# ANTBRAIN.net
KiCad netlist of a schematic drawn in EAGLE
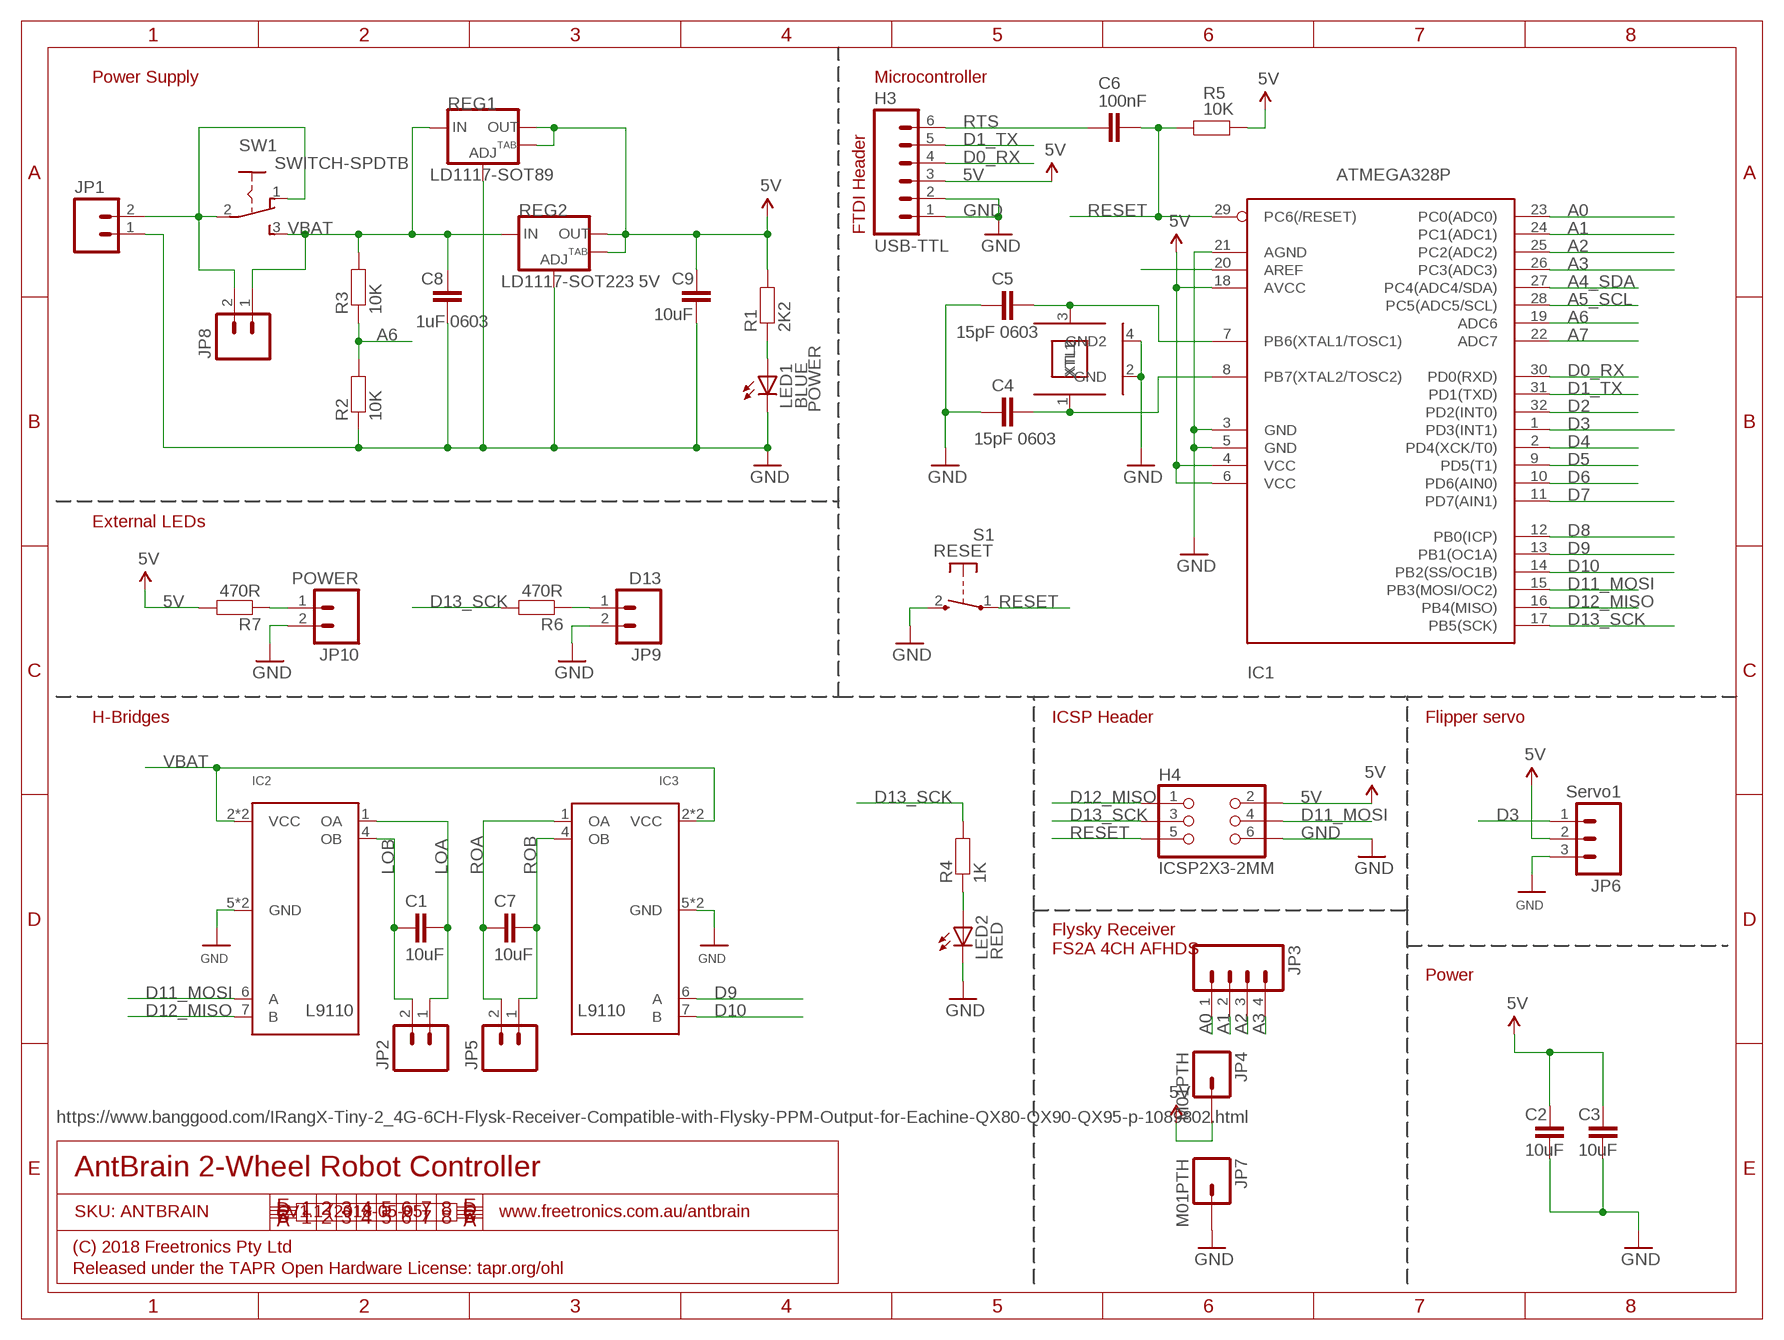
[diagram p0: schematic, sheet 1]

(export (version "E")
  (design (tool "Eeschema 10.0.6"))
  (components
    (comp (ref "C1")
      (value "10uF")
      (footprint "eagle-import:0805")
      (libsource (lib "eagle-import") (part "freetronics-jon_CAP0805"))
    )
    (comp (ref "C2")
      (value "10uF")
      (footprint "eagle-import:0805")
      (libsource (lib "eagle-import") (part "freetronics-jon_CAP0805"))
    )
    (comp (ref "C3")
      (value "10uF")
      (footprint "eagle-import:0805")
      (libsource (lib "eagle-import") (part "freetronics-jon_CAP0805"))
    )
    (comp (ref "C4")
      (value "15pF 0603")
      (footprint "eagle-import:0603")
      (libsource (lib "eagle-import") (part "freetronics-master-v1.1_CAP0603"))
    )
    (comp (ref "C5")
      (value "15pF 0603")
      (footprint "eagle-import:0603")
      (libsource (lib "eagle-import") (part "freetronics-master-v1.1_CAP0603"))
    )
    (comp (ref "C6")
      (value "100nF")
      (footprint "eagle-import:0603")
      (libsource (lib "eagle-import") (part "freetronics-master-v1.1_CAP0603"))
    )
    (comp (ref "C7")
      (value "10uF")
      (footprint "eagle-import:0805")
      (libsource (lib "eagle-import") (part "freetronics-jon_CAP0805"))
    )
    (comp (ref "C8")
      (value "1uF 0603")
      (footprint "eagle-import:0603")
      (libsource (lib "eagle-import") (part "CAP0603"))
    )
    (comp (ref "C9")
      (value "10uF")
      (footprint "eagle-import:0805")
      (libsource (lib "eagle-import") (part "freetronics-jon_CAP0805"))
    )
    (comp (ref "H3")
      (value "USB-TTL")
      (footprint "eagle-import:1X06")
      (libsource (lib "eagle-import") (part "M06SIP"))
    )
    (comp (ref "H4")
      (value "ICSP2X3-2MM")
      (footprint "eagle-import:M2X3-2MM")
      (libsource (lib "eagle-import") (part "ICSP2X3-2MM"))
    )
    (comp (ref "IC1")
      (value "ATMEGA328P")
      (footprint "eagle-import:TQFP32-08")
      (libsource (lib "eagle-import") (part "AVR-MEGA8-AI"))
    )
    (comp (ref "IC2")
      (value "L9110SO8")
      (footprint "eagle-import:SO08")
      (libsource (lib "eagle-import") (part "L9110SO8"))
    )
    (comp (ref "IC3")
      (value "L9110SO8")
      (footprint "eagle-import:SO08")
      (libsource (lib "eagle-import") (part "L9110SO8"))
    )
    (comp (ref "JP1")
      (value "M02PTH")
      (footprint "eagle-import:1X02")
      (libsource (lib "eagle-import") (part "M02PTH"))
    )
    (comp (ref "JP2")
      (value "M02PTH")
      (footprint "eagle-import:1X02")
      (libsource (lib "eagle-import") (part "M02PTH"))
    )
    (comp (ref "JP3")
      (value "M04PTH")
      (footprint "eagle-import:1X04")
      (libsource (lib "eagle-import") (part "M04PTH"))
    )
    (comp (ref "JP4")
      (value "M01PTH")
      (footprint "eagle-import:1X01")
      (libsource (lib "eagle-import") (part "M01PTH"))
    )
    (comp (ref "JP5")
      (value "M02PTH")
      (footprint "eagle-import:1X02")
      (libsource (lib "eagle-import") (part "M02PTH"))
    )
    (comp (ref "JP6")
      (value "Servo1")
      (footprint "eagle-import:1X03")
      (libsource (lib "eagle-import") (part "M03PTH"))
    )
    (comp (ref "JP7")
      (value "M01PTH")
      (footprint "eagle-import:1X01")
      (libsource (lib "eagle-import") (part "M01PTH"))
    )
    (comp (ref "JP8")
      (value "M022MM")
      (footprint "eagle-import:M02-2MM")
      (libsource (lib "eagle-import") (part "M022MM"))
    )
    (comp (ref "JP9")
      (value "D13")
      (footprint "eagle-import:M02-2MM")
      (libsource (lib "eagle-import") (part "M022MM"))
    )
    (comp (ref "JP10")
      (value "POWER")
      (footprint "eagle-import:M02-2MM")
      (libsource (lib "eagle-import") (part "M022MM"))
    )
    (comp (ref "LED1")
      (value "BLUE")
      (footprint "eagle-import:LED-0603")
      (libsource (lib "eagle-import") (part "LED0603"))
    )
    (comp (ref "LED2")
      (value "RED")
      (footprint "eagle-import:LED-0603")
      (libsource (lib "eagle-import") (part "LED0603"))
    )
    (comp (ref "R1")
      (value "2K2")
      (footprint "eagle-import:0603")
      (libsource (lib "eagle-import") (part "RESISTOR0603"))
    )
    (comp (ref "R2")
      (value "10K")
      (footprint "eagle-import:0603")
      (libsource (lib "eagle-import") (part "RESISTOR0603"))
    )
    (comp (ref "R3")
      (value "10K")
      (footprint "eagle-import:0603")
      (libsource (lib "eagle-import") (part "RESISTOR0603"))
    )
    (comp (ref "R4")
      (value "1K")
      (footprint "eagle-import:0603")
      (libsource (lib "eagle-import") (part "RESISTOR0603"))
    )
    (comp (ref "R5")
      (value "10K")
      (footprint "eagle-import:0603")
      (libsource (lib "eagle-import") (part "freetronics-master-v1.1_RESISTOR0603"))
    )
    (comp (ref "R6")
      (value "470R")
      (footprint "eagle-import:0603")
      (libsource (lib "eagle-import") (part "RESISTOR0603"))
    )
    (comp (ref "R7")
      (value "470R")
      (footprint "eagle-import:0603")
      (libsource (lib "eagle-import") (part "RESISTOR0603"))
    )
    (comp (ref "REG1")
      (value "LD1117-SOT89")
      (footprint "eagle-import:SOT89")
      (libsource (lib "eagle-import") (part "V_REG_LM1117SOT89"))
    )
    (comp (ref "REG2")
      (value "LD1117-SOT223 5V")
      (footprint "eagle-import:SOT223")
      (libsource (lib "eagle-import") (part "V_REG_LM1117SOT223"))
    )
    (comp (ref "S1")
      (value "RESET")
      (footprint "eagle-import:TACTILE_SWITCH_SMD_2PIN_TINY")
      (libsource (lib "eagle-import") (part "TAC_SWITCH_2PIN"))
    )
    (comp (ref "SW1")
      (value "SWITCH-SPDTB")
      (footprint "eagle-import:SPDT-2.5MM")
      (libsource (lib "eagle-import") (part "SWITCH-SPDTB"))
    )
    (comp (ref "XTL1")
      (value "16MHz")
      (footprint "eagle-import:CRYSTAL-SMD-3X2")
      (libsource (lib "eagle-import") (part "CRYSTAL-GND3X2"))
    )
  )
  (nets
    (net (code "1") (name "/A0") (class "Default")
      (node (ref "IC1") (pin "23") (pinfunction "PC0(ADC0)_23") (pintype "bidirectional"))
      (node (ref "JP3") (pin "1") (pinfunction "1_1") (pintype "passive"))
    )
    (net (code "2") (name "/A1") (class "Default")
      (node (ref "IC1") (pin "24") (pinfunction "PC1(ADC1)_24") (pintype "bidirectional"))
      (node (ref "JP3") (pin "2") (pinfunction "2_2") (pintype "passive"))
    )
    (net (code "3") (name "/A2") (class "Default")
      (node (ref "IC1") (pin "25") (pinfunction "PC2(ADC2)_25") (pintype "bidirectional"))
      (node (ref "JP3") (pin "3") (pinfunction "3_3") (pintype "passive"))
    )
    (net (code "4") (name "/A3") (class "Default")
      (node (ref "IC1") (pin "26") (pinfunction "PC3(ADC3)_26") (pintype "bidirectional"))
      (node (ref "JP3") (pin "4") (pinfunction "4_4") (pintype "passive"))
    )
    (net (code "5") (name "/A4_SDA") (class "Default")
      (node (ref "IC1") (pin "27") (pinfunction "PC4(ADC4/SDA)_27") (pintype "bidirectional"))
    )
    (net (code "6") (name "/A5_SCL") (class "Default")
      (node (ref "IC1") (pin "28") (pinfunction "PC5(ADC5/SCL)_28") (pintype "bidirectional"))
    )
    (net (code "7") (name "/A6") (class "Default")
      (node (ref "IC1") (pin "19") (pinfunction "ADC6_19") (pintype "bidirectional"))
      (node (ref "R2") (pin "2") (pinfunction "2_2") (pintype "passive"))
      (node (ref "R3") (pin "1") (pinfunction "1_1") (pintype "passive"))
    )
    (net (code "8") (name "/A7") (class "Default")
      (node (ref "IC1") (pin "22") (pinfunction "ADC7_22") (pintype "bidirectional"))
    )
    (net (code "9") (name "/D0_RX") (class "Default")
      (node (ref "H3") (pin "4") (pinfunction "4_4") (pintype "passive"))
      (node (ref "IC1") (pin "30") (pinfunction "PD0(RXD)_30") (pintype "bidirectional"))
    )
    (net (code "10") (name "/D1_TX") (class "Default")
      (node (ref "H3") (pin "5") (pinfunction "5_5") (pintype "passive"))
      (node (ref "IC1") (pin "31") (pinfunction "PD1(TXD)_31") (pintype "bidirectional"))
    )
    (net (code "11") (name "/D2") (class "Default")
      (node (ref "IC1") (pin "32") (pinfunction "PD2(INT0)_32") (pintype "bidirectional"))
    )
    (net (code "12") (name "/D3") (class "Default")
      (node (ref "IC1") (pin "1") (pinfunction "PD3(INT1)_1") (pintype "bidirectional"))
      (node (ref "JP6") (pin "1") (pinfunction "1_1") (pintype "passive"))
    )
    (net (code "13") (name "/D4") (class "Default")
      (node (ref "IC1") (pin "2") (pinfunction "PD4(XCK/T0)_2") (pintype "bidirectional"))
    )
    (net (code "14") (name "/D5") (class "Default")
      (node (ref "IC1") (pin "9") (pinfunction "PD5(T1)_9") (pintype "bidirectional"))
    )
    (net (code "15") (name "/D6") (class "Default")
      (node (ref "IC1") (pin "10") (pinfunction "PD6(AIN0)_10") (pintype "bidirectional"))
    )
    (net (code "16") (name "/D7") (class "Default")
      (node (ref "IC1") (pin "11") (pinfunction "PD7(AIN1)_11") (pintype "bidirectional"))
    )
    (net (code "17") (name "/D8") (class "Default")
      (node (ref "IC1") (pin "12") (pinfunction "PB0(ICP)_12") (pintype "bidirectional"))
    )
    (net (code "18") (name "/D9") (class "Default")
      (node (ref "IC1") (pin "13") (pinfunction "PB1(OC1A)_13") (pintype "bidirectional"))
      (node (ref "IC3") (pin "6") (pinfunction "A_6") (pintype "bidirectional"))
    )
    (net (code "19") (name "/D10") (class "Default")
      (node (ref "IC1") (pin "14") (pinfunction "PB2(SS/OC1B)_14") (pintype "bidirectional"))
      (node (ref "IC3") (pin "7") (pinfunction "B_7") (pintype "bidirectional"))
    )
    (net (code "20") (name "/D11_MOSI") (class "Default")
      (node (ref "H4") (pin "4") (pinfunction "4_4") (pintype "passive"))
      (node (ref "IC1") (pin "15") (pinfunction "PB3(MOSI/OC2)_15") (pintype "bidirectional"))
      (node (ref "IC2") (pin "6") (pinfunction "A_6") (pintype "bidirectional"))
    )
    (net (code "21") (name "/D12_MISO") (class "Default")
      (node (ref "H4") (pin "1") (pinfunction "1_1") (pintype "passive"))
      (node (ref "IC1") (pin "16") (pinfunction "PB4(MISO)_16") (pintype "bidirectional"))
      (node (ref "IC2") (pin "7") (pinfunction "B_7") (pintype "bidirectional"))
    )
    (net (code "22") (name "/D13_SCK") (class "Default")
      (node (ref "H4") (pin "3") (pinfunction "3_3") (pintype "passive"))
      (node (ref "IC1") (pin "17") (pinfunction "PB5(SCK)_17") (pintype "bidirectional"))
      (node (ref "R4") (pin "2") (pinfunction "2_2") (pintype "passive"))
      (node (ref "R6") (pin "2") (pinfunction "2_2") (pintype "passive"))
    )
    (net (code "23") (name "/LOA") (class "Default")
      (node (ref "C1") (pin "1") (pinfunction "1_1") (pintype "passive"))
      (node (ref "IC2") (pin "1") (pinfunction "OA_1") (pintype "bidirectional"))
      (node (ref "JP2") (pin "1") (pinfunction "1_1") (pintype "passive"))
    )
    (net (code "24") (name "/LOB") (class "Default")
      (node (ref "C1") (pin "2") (pinfunction "2_2") (pintype "passive"))
      (node (ref "IC2") (pin "4") (pinfunction "OB_4") (pintype "bidirectional"))
      (node (ref "JP2") (pin "2") (pinfunction "2_2") (pintype "passive"))
    )
    (net (code "25") (name "/RESET") (class "Default")
      (node (ref "C6") (pin "2") (pinfunction "2_2") (pintype "passive"))
      (node (ref "H4") (pin "5") (pinfunction "5_5") (pintype "passive"))
      (node (ref "IC1") (pin "29") (pinfunction "PC6(/RESET)_29") (pintype "bidirectional"))
      (node (ref "R5") (pin "1") (pinfunction "1_1") (pintype "passive"))
      (node (ref "S1") (pin "1") (pinfunction "P_1") (pintype "passive"))
    )
    (net (code "26") (name "/ROA") (class "Default")
      (node (ref "C7") (pin "2") (pinfunction "2_2") (pintype "passive"))
      (node (ref "IC3") (pin "1") (pinfunction "OA_1") (pintype "bidirectional"))
      (node (ref "JP5") (pin "2") (pinfunction "2_2") (pintype "passive"))
    )
    (net (code "27") (name "/ROB") (class "Default")
      (node (ref "C7") (pin "1") (pinfunction "1_1") (pintype "passive"))
      (node (ref "IC3") (pin "4") (pinfunction "OB_4") (pintype "bidirectional"))
      (node (ref "JP5") (pin "1") (pinfunction "1_1") (pintype "passive"))
    )
    (net (code "28") (name "/RTS") (class "Default")
      (node (ref "C6") (pin "1") (pinfunction "1_1") (pintype "passive"))
      (node (ref "H3") (pin "6") (pinfunction "6_6") (pintype "passive"))
    )
    (net (code "29") (name "/VBAT") (class "Default")
      (node (ref "C8") (pin "1") (pinfunction "1_1") (pintype "passive"))
      (node (ref "IC2") (pin "2") (pinfunction "VCC_2") (pintype "bidirectional"))
      (node (ref "IC2") (pin "3") (pinfunction "VCC_3") (pintype "bidirectional"))
      (node (ref "IC3") (pin "2") (pinfunction "VCC_2") (pintype "bidirectional"))
      (node (ref "IC3") (pin "3") (pinfunction "VCC_3") (pintype "bidirectional"))
      (node (ref "JP8") (pin "1") (pinfunction "1_1") (pintype "passive"))
      (node (ref "R3") (pin "2") (pinfunction "2_2") (pintype "passive"))
      (node (ref "REG1") (pin "3") (pinfunction "IN_3") (pintype "input"))
      (node (ref "REG2") (pin "3") (pinfunction "IN_3") (pintype "input"))
      (node (ref "SW1") (pin "3") (pinfunction "3_3") (pintype "passive"))
    )
    (net (code "30") (name "5V") (class "Default")
      (node (ref "C2") (pin "1") (pinfunction "1_1") (pintype "passive"))
      (node (ref "C3") (pin "1") (pinfunction "1_1") (pintype "passive"))
      (node (ref "C9") (pin "1") (pinfunction "1_1") (pintype "passive"))
      (node (ref "H3") (pin "3") (pinfunction "3_3") (pintype "passive"))
      (node (ref "H4") (pin "2") (pinfunction "2_2") (pintype "passive"))
      (node (ref "IC1") (pin "18") (pinfunction "AVCC_18") (pintype "bidirectional"))
      (node (ref "IC1") (pin "4") (pinfunction "VCC_4") (pintype "bidirectional"))
      (node (ref "IC1") (pin "6") (pinfunction "VCC_6") (pintype "bidirectional"))
      (node (ref "JP4") (pin "1") (pinfunction "1_1") (pintype "passive"))
      (node (ref "JP6") (pin "2") (pinfunction "2_2") (pintype "passive"))
      (node (ref "R1") (pin "2") (pinfunction "2_2") (pintype "passive"))
      (node (ref "R5") (pin "2") (pinfunction "2_2") (pintype "passive"))
      (node (ref "R7") (pin "2") (pinfunction "2_2") (pintype "passive"))
      (node (ref "REG1") (pin "2") (pinfunction "OUT_2") (pintype "output"))
      (node (ref "REG1") (pin "4") (pinfunction "OUT_4") (pintype "output"))
      (node (ref "REG2") (pin "2") (pinfunction "OUT_2") (pintype "output"))
      (node (ref "REG2") (pin "4") (pinfunction "OUT_4") (pintype "output"))
    )
    (net (code "31") (name "GND") (class "Default")
      (node (ref "C2") (pin "2") (pinfunction "2_2") (pintype "passive"))
      (node (ref "C3") (pin "2") (pinfunction "2_2") (pintype "passive"))
      (node (ref "C4") (pin "1") (pinfunction "1_1") (pintype "passive"))
      (node (ref "C5") (pin "1") (pinfunction "1_1") (pintype "passive"))
      (node (ref "C8") (pin "2") (pinfunction "2_2") (pintype "passive"))
      (node (ref "C9") (pin "2") (pinfunction "2_2") (pintype "passive"))
      (node (ref "H3") (pin "1") (pinfunction "1_1") (pintype "passive"))
      (node (ref "H3") (pin "2") (pinfunction "2_2") (pintype "passive"))
      (node (ref "H4") (pin "6") (pinfunction "6_6") (pintype "passive"))
      (node (ref "IC1") (pin "21") (pinfunction "AGND_21") (pintype "bidirectional"))
      (node (ref "IC1") (pin "3") (pinfunction "GND_3") (pintype "bidirectional"))
      (node (ref "IC1") (pin "5") (pinfunction "GND_5") (pintype "bidirectional"))
      (node (ref "IC2") (pin "5") (pinfunction "GND_5") (pintype "bidirectional"))
      (node (ref "IC2") (pin "8") (pinfunction "GND_8") (pintype "bidirectional"))
      (node (ref "IC3") (pin "5") (pinfunction "GND_5") (pintype "bidirectional"))
      (node (ref "IC3") (pin "8") (pinfunction "GND_8") (pintype "bidirectional"))
      (node (ref "JP1") (pin "1") (pinfunction "1_1") (pintype "passive"))
      (node (ref "JP10") (pin "2") (pinfunction "2_2") (pintype "passive"))
      (node (ref "JP6") (pin "3") (pinfunction "3_3") (pintype "passive"))
      (node (ref "JP7") (pin "1") (pinfunction "1_1") (pintype "passive"))
      (node (ref "JP9") (pin "2") (pinfunction "2_2") (pintype "passive"))
      (node (ref "LED1") (pin "C") (pinfunction "C_C") (pintype "passive"))
      (node (ref "LED2") (pin "C") (pinfunction "C_C") (pintype "passive"))
      (node (ref "R2") (pin "1") (pinfunction "1_1") (pintype "passive"))
      (node (ref "REG1") (pin "1") (pinfunction "ADJ_1") (pintype "input"))
      (node (ref "REG2") (pin "1") (pinfunction "ADJ_1") (pintype "input"))
      (node (ref "S1") (pin "2") (pinfunction "S_2") (pintype "passive"))
      (node (ref "XTL1") (pin "2") (pinfunction "GND_2") (pintype "bidirectional"))
      (node (ref "XTL1") (pin "4") (pinfunction "GND2_4") (pintype "bidirectional"))
    )
    (net (code "32") (name "Net-(IC1-PB6(XTAL1{slash}TOSC1))") (class "Default")
      (node (ref "C5") (pin "2") (pinfunction "2_2") (pintype "passive"))
      (node (ref "IC1") (pin "7") (pinfunction "PB6(XTAL1/TOSC1)_7") (pintype "bidirectional"))
      (node (ref "XTL1") (pin "3") (pinfunction "XTL2_3") (pintype "bidirectional"))
    )
    (net (code "33") (name "Net-(IC1-PB7(XTAL2{slash}TOSC2))") (class "Default")
      (node (ref "C4") (pin "2") (pinfunction "2_2") (pintype "passive"))
      (node (ref "IC1") (pin "8") (pinfunction "PB7(XTAL2/TOSC2)_8") (pintype "bidirectional"))
      (node (ref "XTL1") (pin "1") (pinfunction "XTL1_1") (pintype "bidirectional"))
    )
    (net (code "34") (name "Net-(JP1-Pad2)") (class "Default")
      (node (ref "JP1") (pin "2") (pinfunction "2_2") (pintype "passive"))
      (node (ref "JP8") (pin "2") (pinfunction "2_2") (pintype "passive"))
      (node (ref "SW1") (pin "1") (pinfunction "1_1") (pintype "passive"))
      (node (ref "SW1") (pin "2") (pinfunction "2_2") (pintype "passive"))
    )
    (net (code "35") (name "Net-(JP9-Pad1)") (class "Default")
      (node (ref "JP9") (pin "1") (pinfunction "1_1") (pintype "passive"))
      (node (ref "R6") (pin "1") (pinfunction "1_1") (pintype "passive"))
    )
    (net (code "36") (name "Net-(JP10-Pad1)") (class "Default")
      (node (ref "JP10") (pin "1") (pinfunction "1_1") (pintype "passive"))
      (node (ref "R7") (pin "1") (pinfunction "1_1") (pintype "passive"))
    )
    (net (code "37") (name "Net-(LED1-PadA)") (class "Default")
      (node (ref "LED1") (pin "A") (pinfunction "A_A") (pintype "passive"))
      (node (ref "R1") (pin "1") (pinfunction "1_1") (pintype "passive"))
    )
    (net (code "38") (name "Net-(LED2-PadA)") (class "Default")
      (node (ref "LED2") (pin "A") (pinfunction "A_A") (pintype "passive"))
      (node (ref "R4") (pin "1") (pinfunction "1_1") (pintype "passive"))
    )
    (net (code "39") (name "unconnected-(IC1-AREF-Pad20)") (class "Default")
      (node (ref "IC1") (pin "20") (pinfunction "AREF_20") (pintype "bidirectional"))
    )
  )
)
